# NusbioMCU.net
KiCad netlist of a schematic drawn in EAGLE
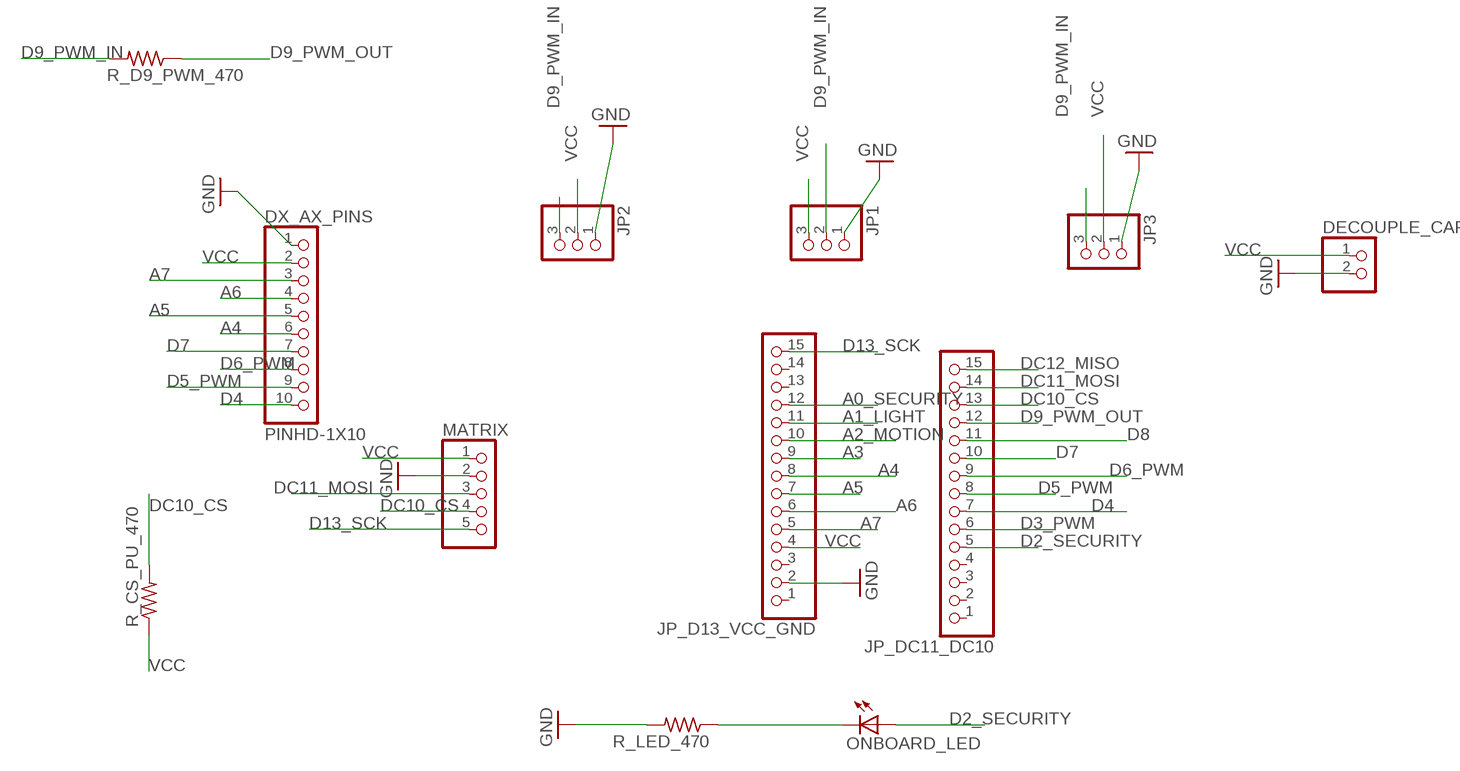
[diagram p0: schematic, sheet 1]

(export (version "E")
  (design (tool "Eeschema 10.0.6"))
  (components
    (comp (ref "DECOUPLE_CAP")
      (value "PINHD-1X2")
      (footprint "eagle-import:1X02")
      (libsource (lib "eagle-import") (part "PINHD-1X2"))
    )
    (comp (ref "DX_AX_PINS")
      (value "PINHD-1X10")
      (footprint "eagle-import:1X10-BIG")
      (libsource (lib "eagle-import") (part "PINHD-1X10"))
    )
    (comp (ref "JP1")
      (value "PINHD-1X3")
      (footprint "eagle-import:1X03")
      (libsource (lib "eagle-import") (part "PINHD-1X3"))
    )
    (comp (ref "JP2")
      (value "PINHD-1X3")
      (footprint "eagle-import:1X03")
      (libsource (lib "eagle-import") (part "PINHD-1X3"))
    )
    (comp (ref "JP3")
      (value "PINHD-1X3")
      (footprint "eagle-import:1X03")
      (libsource (lib "eagle-import") (part "PINHD-1X3"))
    )
    (comp (ref "JP_D13_VCC_GND")
      (value "PINHD-1X15")
      (footprint "eagle-import:1X15")
      (libsource (lib "eagle-import") (part "PINHD-1X15"))
    )
    (comp (ref "JP_DC11_DC10")
      (value "PINHD-1X15")
      (footprint "eagle-import:1X15")
      (libsource (lib "eagle-import") (part "PINHD-1X15"))
    )
    (comp (ref "MATRIX")
      (value "PINHD-1X5")
      (footprint "eagle-import:1X05")
      (libsource (lib "eagle-import") (part "PINHD-1X5"))
    )
    (comp (ref "ONBOARD_LED")
      (value "LEDSMT1206")
      (footprint "eagle-import:1206")
      (libsource (lib "eagle-import") (part "LEDSMT1206"))
    )
    (comp (ref "R_CS_PU_470")
      (value "R-US_R1206")
      (footprint "eagle-import:R1206")
      (libsource (lib "eagle-import") (part "R-US_R1206"))
    )
    (comp (ref "R_D9_PWM_470")
      (value "R-US_R1206")
      (footprint "eagle-import:R1206")
      (libsource (lib "eagle-import") (part "R-US_R1206"))
    )
    (comp (ref "R_LED_470")
      (value "R-US_R1206")
      (footprint "eagle-import:R1206")
      (libsource (lib "eagle-import") (part "R-US_R1206"))
    )
  )
  (nets
    (net (code "1") (name "/A0_SECURITY") (class "Default")
      (node (ref "JP_D13_VCC_GND") (pin "12") (pinfunction "12_12") (pintype "passive"))
    )
    (net (code "2") (name "/A1_LIGHT") (class "Default")
      (node (ref "JP_D13_VCC_GND") (pin "11") (pinfunction "11_11") (pintype "passive"))
    )
    (net (code "3") (name "/A2_MOTION") (class "Default")
      (node (ref "JP_D13_VCC_GND") (pin "10") (pinfunction "10_10") (pintype "passive"))
    )
    (net (code "4") (name "/A3") (class "Default")
      (node (ref "JP_D13_VCC_GND") (pin "9") (pinfunction "9_9") (pintype "passive"))
    )
    (net (code "5") (name "/A4") (class "Default")
      (node (ref "DX_AX_PINS") (pin "6") (pinfunction "6_6") (pintype "passive"))
      (node (ref "JP_D13_VCC_GND") (pin "8") (pinfunction "8_8") (pintype "passive"))
    )
    (net (code "6") (name "/A5") (class "Default")
      (node (ref "DX_AX_PINS") (pin "5") (pinfunction "5_5") (pintype "passive"))
      (node (ref "JP_D13_VCC_GND") (pin "7") (pinfunction "7_7") (pintype "passive"))
    )
    (net (code "7") (name "/A6") (class "Default")
      (node (ref "DX_AX_PINS") (pin "4") (pinfunction "4_4") (pintype "passive"))
      (node (ref "JP_D13_VCC_GND") (pin "6") (pinfunction "6_6") (pintype "passive"))
    )
    (net (code "8") (name "/A7") (class "Default")
      (node (ref "DX_AX_PINS") (pin "3") (pinfunction "3_3") (pintype "passive"))
      (node (ref "JP_D13_VCC_GND") (pin "5") (pinfunction "5_5") (pintype "passive"))
    )
    (net (code "9") (name "/D2_SECURITY") (class "Default")
      (node (ref "JP_DC11_DC10") (pin "5") (pinfunction "5_5") (pintype "passive"))
      (node (ref "ONBOARD_LED") (pin "A") (pinfunction "A_A") (pintype "passive"))
    )
    (net (code "10") (name "/D3_PWM") (class "Default")
      (node (ref "JP_DC11_DC10") (pin "6") (pinfunction "6_6") (pintype "passive"))
    )
    (net (code "11") (name "/D4") (class "Default")
      (node (ref "DX_AX_PINS") (pin "10") (pinfunction "10_10") (pintype "passive"))
      (node (ref "JP_DC11_DC10") (pin "7") (pinfunction "7_7") (pintype "passive"))
    )
    (net (code "12") (name "/D5_PWM") (class "Default")
      (node (ref "DX_AX_PINS") (pin "9") (pinfunction "9_9") (pintype "passive"))
      (node (ref "JP_DC11_DC10") (pin "8") (pinfunction "8_8") (pintype "passive"))
    )
    (net (code "13") (name "/D6_PWM") (class "Default")
      (node (ref "DX_AX_PINS") (pin "8") (pinfunction "8_8") (pintype "passive"))
      (node (ref "JP_DC11_DC10") (pin "9") (pinfunction "9_9") (pintype "passive"))
    )
    (net (code "14") (name "/D7") (class "Default")
      (node (ref "DX_AX_PINS") (pin "7") (pinfunction "7_7") (pintype "passive"))
      (node (ref "JP_DC11_DC10") (pin "10") (pinfunction "10_10") (pintype "passive"))
    )
    (net (code "15") (name "/D8") (class "Default")
      (node (ref "JP_DC11_DC10") (pin "11") (pinfunction "11_11") (pintype "passive"))
    )
    (net (code "16") (name "/D9_PWM_IN") (class "Default")
      (node (ref "JP1") (pin "2") (pinfunction "2_2") (pintype "passive"))
      (node (ref "JP2") (pin "3") (pinfunction "3_3") (pintype "passive"))
      (node (ref "JP3") (pin "3") (pinfunction "3_3") (pintype "passive"))
      (node (ref "R_D9_PWM_470") (pin "2") (pinfunction "2_2") (pintype "passive"))
    )
    (net (code "17") (name "/D9_PWM_OUT") (class "Default")
      (node (ref "JP_DC11_DC10") (pin "12") (pinfunction "12_12") (pintype "passive"))
      (node (ref "R_D9_PWM_470") (pin "1") (pinfunction "1_1") (pintype "passive"))
    )
    (net (code "18") (name "/D13_SCK") (class "Default")
      (node (ref "JP_D13_VCC_GND") (pin "15") (pinfunction "15_15") (pintype "passive"))
      (node (ref "MATRIX") (pin "5") (pinfunction "5_5") (pintype "passive"))
    )
    (net (code "19") (name "/DC10_CS") (class "Default")
      (node (ref "JP_DC11_DC10") (pin "13") (pinfunction "13_13") (pintype "passive"))
      (node (ref "MATRIX") (pin "4") (pinfunction "4_4") (pintype "passive"))
      (node (ref "R_CS_PU_470") (pin "2") (pinfunction "2_2") (pintype "passive"))
    )
    (net (code "20") (name "/DC11_MOSI") (class "Default")
      (node (ref "JP_DC11_DC10") (pin "14") (pinfunction "14_14") (pintype "passive"))
      (node (ref "MATRIX") (pin "3") (pinfunction "3_3") (pintype "passive"))
    )
    (net (code "21") (name "/DC12_MISO") (class "Default")
      (node (ref "JP_DC11_DC10") (pin "15") (pinfunction "15_15") (pintype "passive"))
    )
    (net (code "22") (name "/VCC") (class "Default")
      (node (ref "DECOUPLE_CAP") (pin "1") (pinfunction "1_1") (pintype "passive"))
      (node (ref "DX_AX_PINS") (pin "2") (pinfunction "2_2") (pintype "passive"))
      (node (ref "JP1") (pin "3") (pinfunction "3_3") (pintype "passive"))
      (node (ref "JP2") (pin "2") (pinfunction "2_2") (pintype "passive"))
      (node (ref "JP3") (pin "2") (pinfunction "2_2") (pintype "passive"))
      (node (ref "JP_D13_VCC_GND") (pin "4") (pinfunction "4_4") (pintype "passive"))
      (node (ref "MATRIX") (pin "1") (pinfunction "1_1") (pintype "passive"))
      (node (ref "R_CS_PU_470") (pin "1") (pinfunction "1_1") (pintype "passive"))
    )
    (net (code "23") (name "GND") (class "Default")
      (node (ref "DECOUPLE_CAP") (pin "2") (pinfunction "2_2") (pintype "passive"))
      (node (ref "DX_AX_PINS") (pin "1") (pinfunction "1_1") (pintype "passive"))
      (node (ref "JP1") (pin "1") (pinfunction "1_1") (pintype "passive"))
      (node (ref "JP2") (pin "1") (pinfunction "1_1") (pintype "passive"))
      (node (ref "JP3") (pin "1") (pinfunction "1_1") (pintype "passive"))
      (node (ref "JP_D13_VCC_GND") (pin "2") (pinfunction "2_2") (pintype "passive"))
      (node (ref "MATRIX") (pin "2") (pinfunction "2_2") (pintype "passive"))
      (node (ref "R_LED_470") (pin "2") (pinfunction "2_2") (pintype "passive"))
    )
    (net (code "24") (name "Net-(ONBOARD_LED-PadC)") (class "Default")
      (node (ref "ONBOARD_LED") (pin "C") (pinfunction "C_C") (pintype "passive"))
      (node (ref "R_LED_470") (pin "1") (pinfunction "1_1") (pintype "passive"))
    )
    (net (code "25") (name "unconnected-(JP_D13_VCC_GND-Pad1)") (class "Default")
      (node (ref "JP_D13_VCC_GND") (pin "1") (pinfunction "1_1") (pintype "passive"))
    )
    (net (code "26") (name "unconnected-(JP_D13_VCC_GND-Pad3)") (class "Default")
      (node (ref "JP_D13_VCC_GND") (pin "3") (pinfunction "3_3") (pintype "passive"))
    )
    (net (code "27") (name "unconnected-(JP_D13_VCC_GND-Pad13)") (class "Default")
      (node (ref "JP_D13_VCC_GND") (pin "13") (pinfunction "13_13") (pintype "passive"))
    )
    (net (code "28") (name "unconnected-(JP_D13_VCC_GND-Pad14)") (class "Default")
      (node (ref "JP_D13_VCC_GND") (pin "14") (pinfunction "14_14") (pintype "passive"))
    )
    (net (code "29") (name "unconnected-(JP_DC11_DC10-Pad1)") (class "Default")
      (node (ref "JP_DC11_DC10") (pin "1") (pinfunction "1_1") (pintype "passive"))
    )
    (net (code "30") (name "unconnected-(JP_DC11_DC10-Pad2)") (class "Default")
      (node (ref "JP_DC11_DC10") (pin "2") (pinfunction "2_2") (pintype "passive"))
    )
    (net (code "31") (name "unconnected-(JP_DC11_DC10-Pad3)") (class "Default")
      (node (ref "JP_DC11_DC10") (pin "3") (pinfunction "3_3") (pintype "passive"))
    )
    (net (code "32") (name "unconnected-(JP_DC11_DC10-Pad4)") (class "Default")
      (node (ref "JP_DC11_DC10") (pin "4") (pinfunction "4_4") (pintype "passive"))
    )
  )
)
